# 4-port.net
KiCad netlist of a schematic drawn in EAGLE
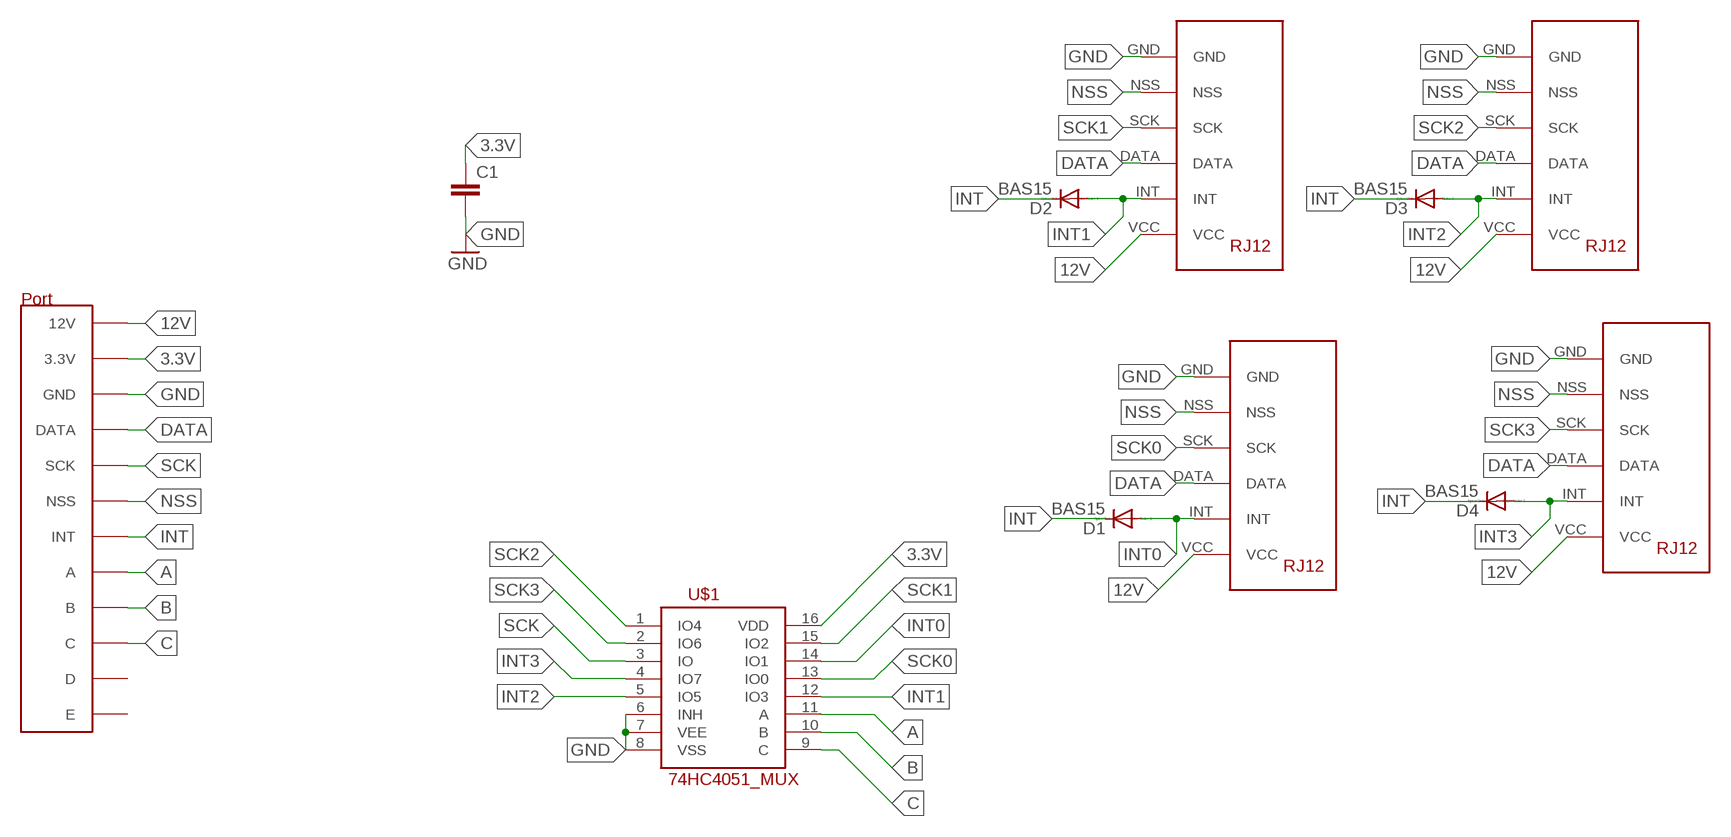
[diagram p0: schematic, sheet 1]

(export (version "E")
  (design (tool "Eeschema 10.0.6"))
  (components
    (comp (ref "C1")
      (value "C-EUC1206")
      (footprint "eagle-import:C1206")
      (libsource (lib "eagle-import") (part "C-EUC1206"))
    )
    (comp (ref "D1")
      (value "BAS15")
      (footprint "eagle-import:DO34-7")
      (libsource (lib "eagle-import") (part "BAS15"))
    )
    (comp (ref "D2")
      (value "BAS15")
      (footprint "eagle-import:DO34-7")
      (libsource (lib "eagle-import") (part "BAS15"))
    )
    (comp (ref "D3")
      (value "BAS15")
      (footprint "eagle-import:DO34-7")
      (libsource (lib "eagle-import") (part "BAS15"))
    )
    (comp (ref "D4")
      (value "BAS15")
      (footprint "eagle-import:DO34-7")
      (libsource (lib "eagle-import") (part "BAS15"))
    )
    (comp (ref "U$1")
      (value "74HC4051_MUX")
      (footprint "eagle-import:SO16")
      (libsource (lib "eagle-import") (part "74HC4051_MUX"))
    )
    (comp (ref "U$2")
      (value "RJ12SMD")
      (footprint "eagle-import:RJ12_SMD")
      (libsource (lib "eagle-import") (part "RJ12SMD"))
    )
    (comp (ref "U$3")
      (value "HUB_PORT")
      (footprint "eagle-import:HUB_PORT")
      (libsource (lib "eagle-import") (part "HUB_PORT"))
    )
    (comp (ref "U$4")
      (value "RJ12SMD")
      (footprint "eagle-import:RJ12_SMD")
      (libsource (lib "eagle-import") (part "RJ12SMD"))
    )
    (comp (ref "U$5")
      (value "RJ12SMD")
      (footprint "eagle-import:RJ12_SMD")
      (libsource (lib "eagle-import") (part "RJ12SMD"))
    )
    (comp (ref "U$7")
      (value "RJ12SMD")
      (footprint "eagle-import:RJ12_SMD")
      (libsource (lib "eagle-import") (part "RJ12SMD"))
    )
  )
  (nets
    (net (code "1") (name "3.3V") (class "Default")
      (node (ref "C1") (pin "1") (pinfunction "1_1") (pintype "passive"))
      (node (ref "U$1") (pin "16") (pinfunction "VDD_16") (pintype "bidirectional"))
      (node (ref "U$3") (pin "3.3V") (pinfunction "3.3V_3.3V") (pintype "bidirectional"))
    )
    (net (code "2") (name "12V") (class "Default")
      (node (ref "U$2") (pin "VCC") (pinfunction "VCC_VCC") (pintype "bidirectional"))
      (node (ref "U$3") (pin "12V") (pinfunction "12V_12V") (pintype "bidirectional"))
      (node (ref "U$4") (pin "VCC") (pinfunction "VCC_VCC") (pintype "bidirectional"))
      (node (ref "U$5") (pin "VCC") (pinfunction "VCC_VCC") (pintype "bidirectional"))
      (node (ref "U$7") (pin "VCC") (pinfunction "VCC_VCC") (pintype "bidirectional"))
    )
    (net (code "3") (name "A") (class "Default")
      (node (ref "U$1") (pin "11") (pinfunction "A_11") (pintype "bidirectional"))
      (node (ref "U$3") (pin "A") (pinfunction "A_A") (pintype "bidirectional"))
    )
    (net (code "4") (name "B") (class "Default")
      (node (ref "U$1") (pin "10") (pinfunction "B_10") (pintype "bidirectional"))
      (node (ref "U$3") (pin "B") (pinfunction "B_B") (pintype "bidirectional"))
    )
    (net (code "5") (name "C") (class "Default")
      (node (ref "U$1") (pin "9") (pinfunction "C_9") (pintype "bidirectional"))
      (node (ref "U$3") (pin "C") (pinfunction "C_C") (pintype "bidirectional"))
    )
    (net (code "6") (name "DATA") (class "Default")
      (node (ref "U$2") (pin "DATA") (pinfunction "DATA_DATA") (pintype "bidirectional"))
      (node (ref "U$3") (pin "DATA") (pinfunction "DATA_DATA") (pintype "bidirectional"))
      (node (ref "U$4") (pin "DATA") (pinfunction "DATA_DATA") (pintype "bidirectional"))
      (node (ref "U$5") (pin "DATA") (pinfunction "DATA_DATA") (pintype "bidirectional"))
      (node (ref "U$7") (pin "DATA") (pinfunction "DATA_DATA") (pintype "bidirectional"))
    )
    (net (code "7") (name "GND") (class "Default")
      (node (ref "C1") (pin "2") (pinfunction "2_2") (pintype "passive"))
      (node (ref "U$1") (pin "6") (pinfunction "INH_6") (pintype "bidirectional"))
      (node (ref "U$1") (pin "7") (pinfunction "VEE_7") (pintype "bidirectional"))
      (node (ref "U$1") (pin "8") (pinfunction "VSS_8") (pintype "bidirectional"))
      (node (ref "U$2") (pin "GND") (pinfunction "GND_GND") (pintype "bidirectional"))
      (node (ref "U$3") (pin "GND") (pinfunction "GND_GND") (pintype "bidirectional"))
      (node (ref "U$4") (pin "GND") (pinfunction "GND_GND") (pintype "bidirectional"))
      (node (ref "U$5") (pin "GND") (pinfunction "GND_GND") (pintype "bidirectional"))
      (node (ref "U$7") (pin "GND") (pinfunction "GND_GND") (pintype "bidirectional"))
    )
    (net (code "8") (name "INT") (class "Default")
      (node (ref "D1") (pin "C") (pinfunction "C_C") (pintype "passive"))
      (node (ref "D2") (pin "C") (pinfunction "C_C") (pintype "passive"))
      (node (ref "D3") (pin "C") (pinfunction "C_C") (pintype "passive"))
      (node (ref "D4") (pin "C") (pinfunction "C_C") (pintype "passive"))
      (node (ref "U$3") (pin "INT") (pinfunction "INT_INT") (pintype "bidirectional"))
    )
    (net (code "9") (name "INT0") (class "Default")
      (node (ref "D1") (pin "A") (pinfunction "A_A") (pintype "passive"))
      (node (ref "U$1") (pin "14") (pinfunction "IO1_14") (pintype "bidirectional"))
      (node (ref "U$2") (pin "INT") (pinfunction "INT_INT") (pintype "bidirectional"))
    )
    (net (code "10") (name "INT1") (class "Default")
      (node (ref "D2") (pin "A") (pinfunction "A_A") (pintype "passive"))
      (node (ref "U$1") (pin "12") (pinfunction "IO3_12") (pintype "bidirectional"))
      (node (ref "U$4") (pin "INT") (pinfunction "INT_INT") (pintype "bidirectional"))
    )
    (net (code "11") (name "INT2") (class "Default")
      (node (ref "D3") (pin "A") (pinfunction "A_A") (pintype "passive"))
      (node (ref "U$1") (pin "5") (pinfunction "IO5_5") (pintype "bidirectional"))
      (node (ref "U$5") (pin "INT") (pinfunction "INT_INT") (pintype "bidirectional"))
    )
    (net (code "12") (name "INT3") (class "Default")
      (node (ref "D4") (pin "A") (pinfunction "A_A") (pintype "passive"))
      (node (ref "U$1") (pin "4") (pinfunction "IO7_4") (pintype "bidirectional"))
      (node (ref "U$7") (pin "INT") (pinfunction "INT_INT") (pintype "bidirectional"))
    )
    (net (code "13") (name "NSS") (class "Default")
      (node (ref "U$2") (pin "NSS") (pinfunction "NSS_NSS") (pintype "bidirectional"))
      (node (ref "U$3") (pin "NSS") (pinfunction "NSS_NSS") (pintype "bidirectional"))
      (node (ref "U$4") (pin "NSS") (pinfunction "NSS_NSS") (pintype "bidirectional"))
      (node (ref "U$5") (pin "NSS") (pinfunction "NSS_NSS") (pintype "bidirectional"))
      (node (ref "U$7") (pin "NSS") (pinfunction "NSS_NSS") (pintype "bidirectional"))
    )
    (net (code "14") (name "SCK") (class "Default")
      (node (ref "U$1") (pin "3") (pinfunction "IO_3") (pintype "bidirectional"))
      (node (ref "U$3") (pin "SCK") (pinfunction "SCK_SCK") (pintype "bidirectional"))
    )
    (net (code "15") (name "SCK0") (class "Default")
      (node (ref "U$1") (pin "13") (pinfunction "IO0_13") (pintype "bidirectional"))
      (node (ref "U$2") (pin "SCK") (pinfunction "SCK_SCK") (pintype "bidirectional"))
    )
    (net (code "16") (name "SCK1") (class "Default")
      (node (ref "U$1") (pin "15") (pinfunction "IO2_15") (pintype "bidirectional"))
      (node (ref "U$4") (pin "SCK") (pinfunction "SCK_SCK") (pintype "bidirectional"))
    )
    (net (code "17") (name "SCK2") (class "Default")
      (node (ref "U$1") (pin "1") (pinfunction "IO4_1") (pintype "bidirectional"))
      (node (ref "U$5") (pin "SCK") (pinfunction "SCK_SCK") (pintype "bidirectional"))
    )
    (net (code "18") (name "SCK3") (class "Default")
      (node (ref "U$1") (pin "2") (pinfunction "IO6_2") (pintype "bidirectional"))
      (node (ref "U$7") (pin "SCK") (pinfunction "SCK_SCK") (pintype "bidirectional"))
    )
    (net (code "19") (name "unconnected-(U$3-PadD)") (class "Default")
      (node (ref "U$3") (pin "D") (pinfunction "D_D") (pintype "bidirectional"))
    )
    (net (code "20") (name "unconnected-(U$3-PadE)") (class "Default")
      (node (ref "U$3") (pin "E") (pinfunction "E_E") (pintype "bidirectional"))
    )
  )
)
